# RP2040_MCU.net
KiCad netlist of a schematic drawn in Altium Designer
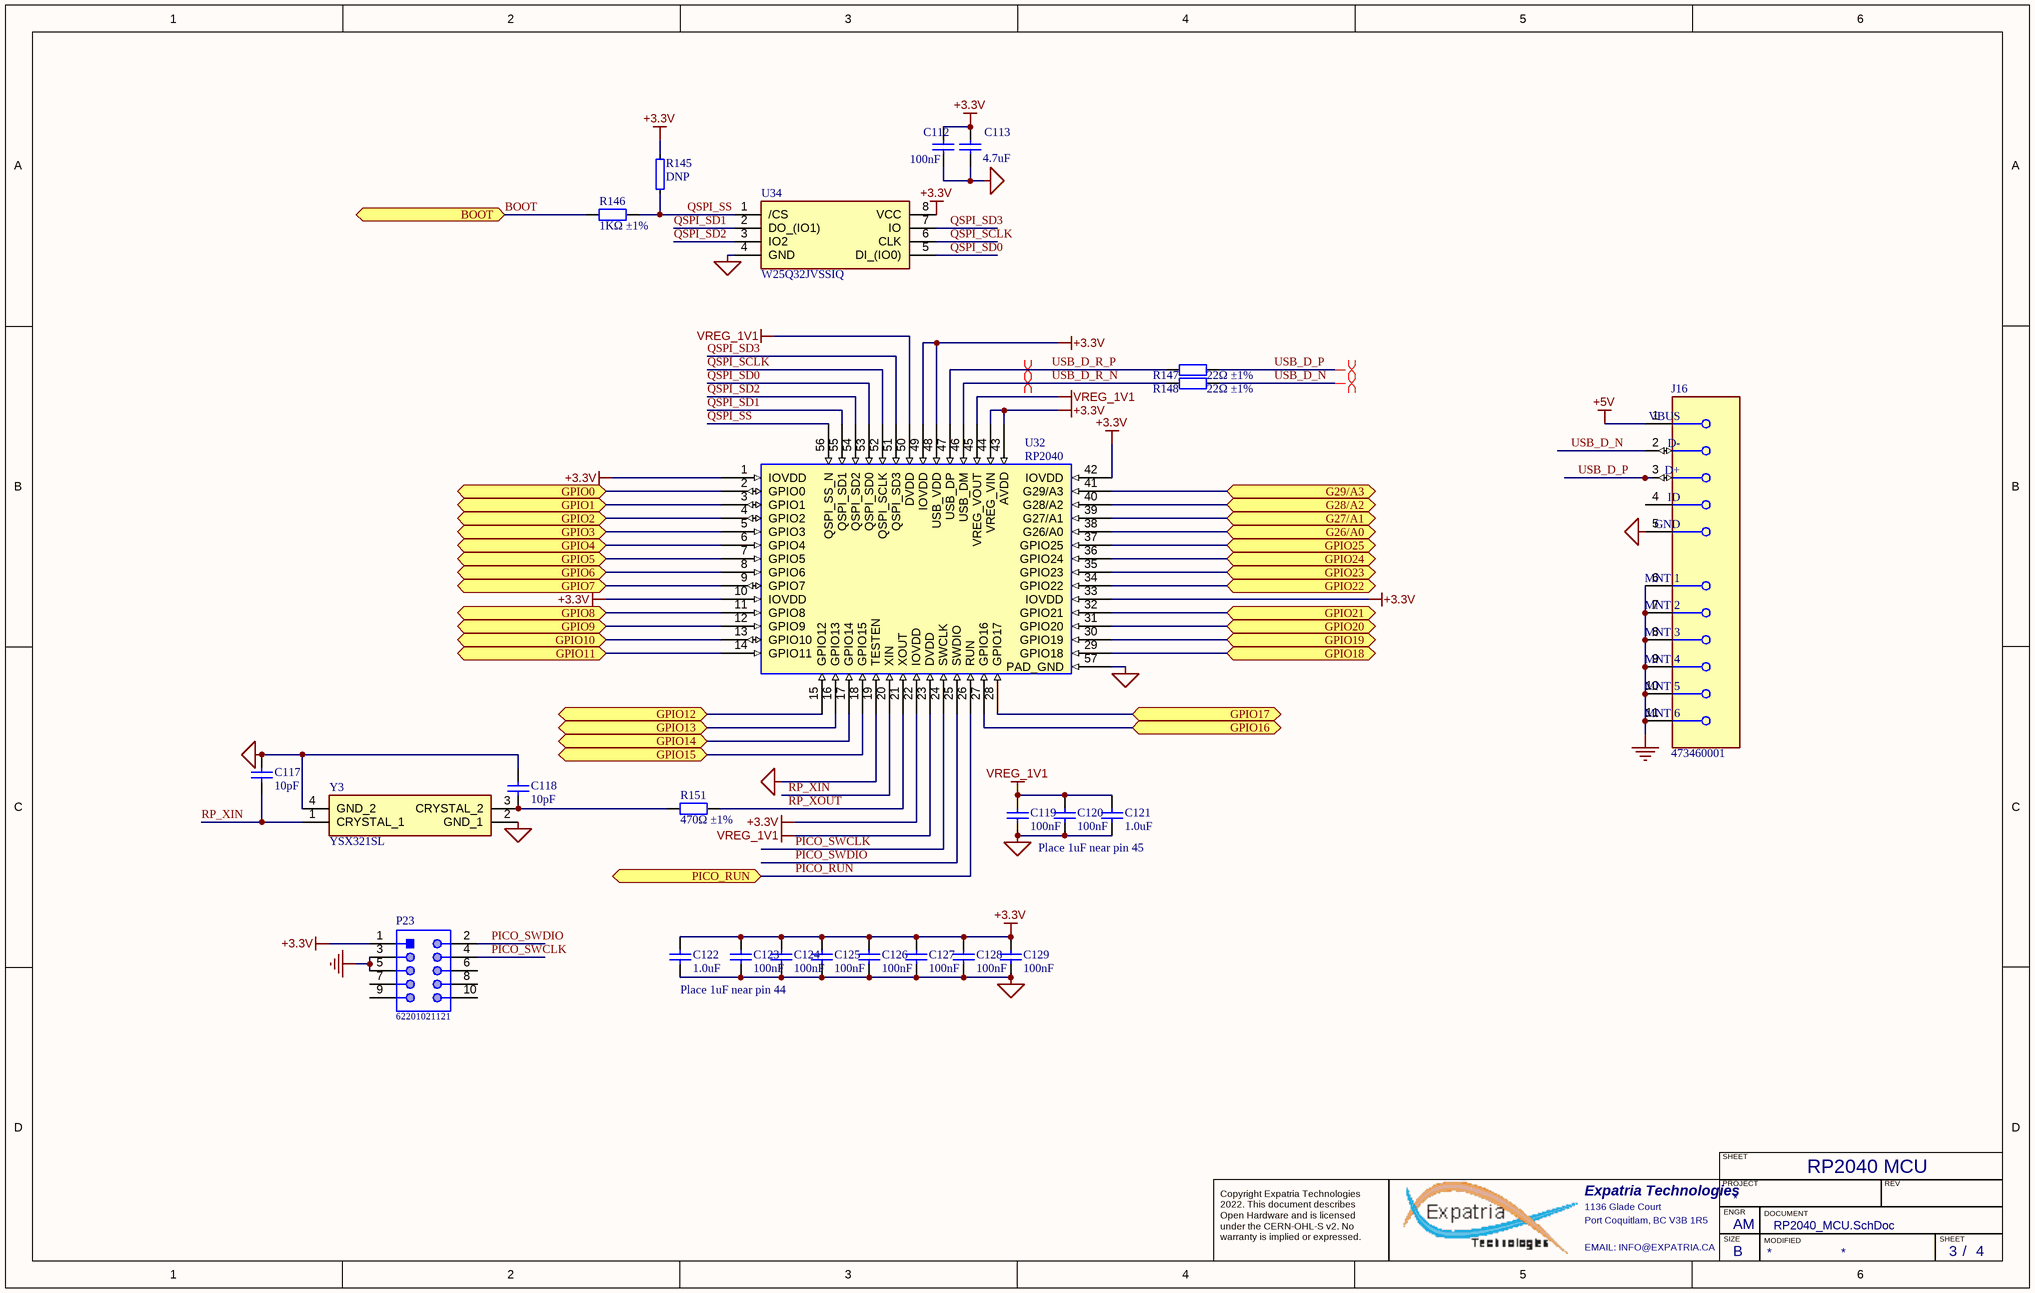
[diagram p0: RP2040_MCU.SchDoc]

(export (version "E")
  (design (tool "Eeschema 10.0.6"))
  (components
    (comp (ref "C112")
      (value "100nF")
      (footprint "0402_C")
      (description "Chip capacitors")
      (fields
        (field (name "MANUFACTURER") "Samsung Electro-Mechanics")
        (field (name "PARTNUMBER") "CL05B104KO5NNNC")
      )
      (libsource (lib "Cap") (part "0402 100nF (104) 10% 16V"))
    )
    (comp (ref "C113")
      (value "4.7uF")
      (footprint "0402_C")
      (description "Chip capacitor")
      (fields
        (field (name "MANUFACTURER") "Samsung Electro-Mechanics")
        (field (name "PARTNUMBER") "CL05A475MP5NRNC")
      )
      (libsource (lib "Cap") (part "0402 4.7uF (475) 20% 10V"))
    )
    (comp (ref "C117")
      (value "10pF")
      (footprint "0402_C")
      (description "Chip capacitors")
      (fields
        (field (name "MANUFACTURER") "Samsung Electro-Mechanics")
        (field (name "PARTNUMBER") "CL05C100JB5NNNC")
      )
      (libsource (lib "Cap") (part "0402 10pF (100) 5% 50V"))
    )
    (comp (ref "C118")
      (value "10pF")
      (footprint "0402_C")
      (description "Chip capacitors")
      (fields
        (field (name "MANUFACTURER") "Samsung Electro-Mechanics")
        (field (name "PARTNUMBER") "CL05C100JB5NNNC")
      )
      (libsource (lib "Cap") (part "0402 10pF (100) 5% 50V"))
    )
    (comp (ref "C119")
      (value "100nF")
      (footprint "0402_C")
      (description "Chip capacitors")
      (fields
        (field (name "MANUFACTURER") "Samsung Electro-Mechanics")
        (field (name "PARTNUMBER") "CL05B104KO5NNNC")
      )
      (libsource (lib "Cap") (part "0402 100nF (104) 10% 16V"))
    )
    (comp (ref "C120")
      (value "100nF")
      (footprint "0402_C")
      (description "Chip capacitors")
      (fields
        (field (name "MANUFACTURER") "Samsung Electro-Mechanics")
        (field (name "PARTNUMBER") "CL05B104KO5NNNC")
      )
      (libsource (lib "Cap") (part "0402 100nF (104) 10% 16V"))
    )
    (comp (ref "C121")
      (value "1.0uF")
      (footprint "0402_C")
      (description "Chip capacitor")
      (fields
        (field (name "MANUFACTURER") "Samsung Electro-Mechanics")
        (field (name "PARTNUMBER") "CL05A105KA5NQNC")
      )
      (libsource (lib "Cap") (part "0402 1.0uF (105) 10% 25V"))
    )
    (comp (ref "C122")
      (value "1.0uF")
      (footprint "0402_C")
      (description "Chip capacitor")
      (fields
        (field (name "MANUFACTURER") "Samsung Electro-Mechanics")
        (field (name "PARTNUMBER") "CL05A105KA5NQNC")
      )
      (libsource (lib "Cap") (part "0402 1.0uF (105) 10% 25V"))
    )
    (comp (ref "C123")
      (value "100nF")
      (footprint "0402_C")
      (description "Chip capacitors")
      (fields
        (field (name "MANUFACTURER") "Samsung Electro-Mechanics")
        (field (name "PARTNUMBER") "CL05B104KO5NNNC")
      )
      (libsource (lib "Cap") (part "0402 100nF (104) 10% 16V"))
    )
    (comp (ref "C124")
      (value "100nF")
      (footprint "0402_C")
      (description "Chip capacitors")
      (fields
        (field (name "MANUFACTURER") "Samsung Electro-Mechanics")
        (field (name "PARTNUMBER") "CL05B104KO5NNNC")
      )
      (libsource (lib "Cap") (part "0402 100nF (104) 10% 16V"))
    )
    (comp (ref "C125")
      (value "100nF")
      (footprint "0402_C")
      (description "Chip capacitors")
      (fields
        (field (name "MANUFACTURER") "Samsung Electro-Mechanics")
        (field (name "PARTNUMBER") "CL05B104KO5NNNC")
      )
      (libsource (lib "Cap") (part "0402 100nF (104) 10% 16V"))
    )
    (comp (ref "C126")
      (value "100nF")
      (footprint "0402_C")
      (description "Chip capacitors")
      (fields
        (field (name "MANUFACTURER") "Samsung Electro-Mechanics")
        (field (name "PARTNUMBER") "CL05B104KO5NNNC")
      )
      (libsource (lib "Cap") (part "0402 100nF (104) 10% 16V"))
    )
    (comp (ref "C127")
      (value "100nF")
      (footprint "0402_C")
      (description "Chip capacitors")
      (fields
        (field (name "MANUFACTURER") "Samsung Electro-Mechanics")
        (field (name "PARTNUMBER") "CL05B104KO5NNNC")
      )
      (libsource (lib "Cap") (part "0402 100nF (104) 10% 16V"))
    )
    (comp (ref "C128")
      (value "100nF")
      (footprint "0402_C")
      (description "Chip capacitors")
      (fields
        (field (name "MANUFACTURER") "Samsung Electro-Mechanics")
        (field (name "PARTNUMBER") "CL05B104KO5NNNC")
      )
      (libsource (lib "Cap") (part "0402 100nF (104) 10% 16V"))
    )
    (comp (ref "C129")
      (value "100nF")
      (footprint "0402_C")
      (description "Chip capacitors")
      (fields
        (field (name "MANUFACTURER") "Samsung Electro-Mechanics")
        (field (name "PARTNUMBER") "CL05B104KO5NNNC")
      )
      (libsource (lib "Cap") (part "0402 100nF (104) 10% 16V"))
    )
    (comp (ref "J16")
      (value "473460001")
      (footprint "FP-473460001-MFG")
      (description "CONN RCPT USB2.0 MICRO B SMD R/A")
      (fields
        (field (name "OCTOPART") "https://octopart.com/47346-0001-molex-7164928")
        (field (name "MANUFACTURER") "Molex")
      )
      (libsource (lib "Altium Content Vault") (part "53ae1f1d9b557310b43ca686e5bb76a"))
    )
    (comp (ref "P23")
      (value "62201021121")
      (footprint "62201021121")
      (description "THT Vertical Pin Header WR-PHD, Pitch 1.27 mm, Dual Row, 10 pins")
      (fields (field (name "MANUFACTURER") "Wurth Elektronik") (field (name "PUBLISHER") "WurthElektronik"))
      (libsource (lib "Altium Content Vault") (part "WE-CN-2P-M-R10"))
    )
    (comp (ref "R145")
      (value "DNP")
      (footprint "0402")
      (description "Resistor, ±5%, 0.05W")
      (fields (field (name "PART NUMBER") "R0201-0R") (field (name "PUBLISHER") "Nordic Semiconductor"))
      (libsource (lib "Passives") (part "RES"))
    )
    (comp (ref "R146")
      (value "1KΩ ±1%")
      (footprint "0402_R")
      (description "Chip resistor")
      (fields (field (name "MANUFACTURER") "Uniroyal Elec") (field (name "PARTNUMBER") "0402WGF1001TCE"))
      (libsource (lib "RES") (part "0402 1K (1001) 1%"))
    )
    (comp (ref "R147")
      (value "22Ω ±1%")
      (footprint "0402_R")
      (description "Chip resistor")
      (fields (field (name "MANUFACTURER") "Uniroyal Elec") (field (name "PARTNUMBER") "0402WGF220JTCE"))
      (libsource (lib "RES") (part "0402 22R (22R0) 1%"))
    )
    (comp (ref "R148")
      (value "22Ω ±1%")
      (footprint "0402_R")
      (description "Chip resistor")
      (fields (field (name "MANUFACTURER") "Uniroyal Elec") (field (name "PARTNUMBER") "0402WGF220JTCE"))
      (libsource (lib "RES") (part "0402 22R (22R0) 1%"))
    )
    (comp (ref "R151")
      (value "470Ω ±1%")
      (footprint "0402_R")
      (description "Chip resistor")
      (fields (field (name "MANUFACTURER") "Uniroyal Elec") (field (name "PARTNUMBER") "0402WGF4700TCE"))
      (libsource (lib "RES") (part "0402 470R (4700) 1%"))
    )
    (comp (ref "U32")
      (value "RP2040")
      (footprint "RP2040")
      (description "RP2040 First MCU from RPI")
      (libsource (lib "Universal_CNC_Breakout") (part "RP2040"))
    )
    (comp (ref "U34")
      (value "W25Q32JVSSIQ")
      (footprint "SamacSys:SOIC127P780X195-8N")
      (description "SPI Flash")
      (fields
        (field (name "MANUFACTURER_PART_NUMBER") "W25Q128JVSIQ TR")
        (field (name "MOUSER PART NUMBER") "454-W25Q128JVSIQTR")
      )
      (libsource (lib "*") (part "W25Q128JVSIQ_TR"))
    )
    (comp (ref "Y3")
      (value "YSX321SL")
      (footprint "SamacSys:YSX321SL")
      (description "Crystal or Oscillator")
      (libsource (lib "*") (part "YSX321SL"))
    )
  )
  (nets
    (net (code "1") (name "+3.3V") (class "Default")
      (node (ref "C112") (pin "2") (pinfunction "2_2") (pintype "passive"))
      (node (ref "C113") (pin "2") (pinfunction "2_2") (pintype "passive"))
      (node (ref "C122") (pin "2") (pinfunction "2_2") (pintype "passive"))
      (node (ref "C123") (pin "2") (pinfunction "2_2") (pintype "passive"))
      (node (ref "C124") (pin "2") (pinfunction "2_2") (pintype "passive"))
      (node (ref "C125") (pin "2") (pinfunction "2_2") (pintype "passive"))
      (node (ref "C126") (pin "2") (pinfunction "2_2") (pintype "passive"))
      (node (ref "C127") (pin "2") (pinfunction "2_2") (pintype "passive"))
      (node (ref "C128") (pin "2") (pinfunction "2_2") (pintype "passive"))
      (node (ref "C129") (pin "2") (pinfunction "2_2") (pintype "passive"))
      (node (ref "P23") (pin "1") (pinfunction "1_1") (pintype "passive"))
      (node (ref "R145") (pin "2") (pinfunction "2_2") (pintype "passive"))
      (node (ref "U32") (pin "1") (pinfunction "IOVDD_1") (pintype "input"))
      (node (ref "U32") (pin "10") (pinfunction "IOVDD_10") (pintype "input"))
      (node (ref "U32") (pin "22") (pinfunction "IOVDD_22") (pintype "input"))
      (node (ref "U32") (pin "33") (pinfunction "IOVDD_33") (pintype "input"))
      (node (ref "U32") (pin "42") (pinfunction "IOVDD_42") (pintype "input"))
      (node (ref "U32") (pin "43") (pinfunction "AVDD_43") (pintype "input"))
      (node (ref "U32") (pin "44") (pinfunction "VREG_VIN_44") (pintype "input"))
      (node (ref "U32") (pin "48") (pinfunction "USB_VDD_48") (pintype "input"))
      (node (ref "U32") (pin "49") (pinfunction "IOVDD_49") (pintype "input"))
      (node (ref "U34") (pin "8") (pinfunction "VCC_8") (pintype "passive"))
    )
    (net (code "2") (name "+5V") (class "Default")
      (node (ref "J16") (pin "1") (pinfunction "VBUS_1") (pintype "power_in"))
    )
    (net (code "3") (name "/BOOT") (class "Default")
      (node (ref "R146") (pin "1") (pinfunction "1_1") (pintype "passive"))
    )
    (net (code "4") (name "/G26{slash}A0") (class "Default")
      (node (ref "U32") (pin "38") (pinfunction "G26/A0_38") (pintype "input"))
    )
    (net (code "5") (name "/G27{slash}A1") (class "Default")
      (node (ref "U32") (pin "39") (pinfunction "G27/A1_39") (pintype "input"))
    )
    (net (code "6") (name "/G28{slash}A2") (class "Default")
      (node (ref "U32") (pin "40") (pinfunction "G28/A2_40") (pintype "input"))
    )
    (net (code "7") (name "/G29{slash}A3") (class "Default")
      (node (ref "U32") (pin "41") (pinfunction "G29/A3_41") (pintype "input"))
    )
    (net (code "8") (name "/GPIO0") (class "Default")
      (node (ref "U32") (pin "2") (pinfunction "GPIO0_2") (pintype "bidirectional"))
    )
    (net (code "9") (name "/GPIO1") (class "Default")
      (node (ref "U32") (pin "3") (pinfunction "GPIO1_3") (pintype "bidirectional"))
    )
    (net (code "10") (name "/GPIO2") (class "Default")
      (node (ref "U32") (pin "4") (pinfunction "GPIO2_4") (pintype "bidirectional"))
    )
    (net (code "11") (name "/GPIO3") (class "Default")
      (node (ref "U32") (pin "5") (pinfunction "GPIO3_5") (pintype "input"))
    )
    (net (code "12") (name "/GPIO4") (class "Default")
      (node (ref "U32") (pin "6") (pinfunction "GPIO4_6") (pintype "input"))
    )
    (net (code "13") (name "/GPIO5") (class "Default")
      (node (ref "U32") (pin "7") (pinfunction "GPIO5_7") (pintype "input"))
    )
    (net (code "14") (name "/GPIO6") (class "Default")
      (node (ref "U32") (pin "8") (pinfunction "GPIO6_8") (pintype "input"))
    )
    (net (code "15") (name "/GPIO7") (class "Default")
      (node (ref "U32") (pin "9") (pinfunction "GPIO7_9") (pintype "bidirectional"))
    )
    (net (code "16") (name "/GPIO8") (class "Default")
      (node (ref "U32") (pin "11") (pinfunction "GPIO8_11") (pintype "input"))
    )
    (net (code "17") (name "/GPIO9") (class "Default")
      (node (ref "U32") (pin "12") (pinfunction "GPIO9_12") (pintype "input"))
    )
    (net (code "18") (name "/GPIO10") (class "Default")
      (node (ref "U32") (pin "13") (pinfunction "GPIO10_13") (pintype "bidirectional"))
    )
    (net (code "19") (name "/GPIO11") (class "Default")
      (node (ref "U32") (pin "14") (pinfunction "GPIO11_14") (pintype "input"))
    )
    (net (code "20") (name "/GPIO12") (class "Default")
      (node (ref "U32") (pin "15") (pinfunction "GPIO12_15") (pintype "input"))
    )
    (net (code "21") (name "/GPIO13") (class "Default")
      (node (ref "U32") (pin "16") (pinfunction "GPIO13_16") (pintype "input"))
    )
    (net (code "22") (name "/GPIO14") (class "Default")
      (node (ref "U32") (pin "17") (pinfunction "GPIO14_17") (pintype "input"))
    )
    (net (code "23") (name "/GPIO15") (class "Default")
      (node (ref "U32") (pin "18") (pinfunction "GPIO15_18") (pintype "input"))
    )
    (net (code "24") (name "/GPIO16") (class "Default")
      (node (ref "U32") (pin "27") (pinfunction "GPIO16_27") (pintype "input"))
    )
    (net (code "25") (name "/GPIO17") (class "Default")
      (node (ref "U32") (pin "28") (pinfunction "GPIO17_28") (pintype "input"))
    )
    (net (code "26") (name "/GPIO18") (class "Default")
      (node (ref "U32") (pin "29") (pinfunction "GPIO18_29") (pintype "input"))
    )
    (net (code "27") (name "/GPIO19") (class "Default")
      (node (ref "U32") (pin "30") (pinfunction "GPIO19_30") (pintype "input"))
    )
    (net (code "28") (name "/GPIO20") (class "Default")
      (node (ref "U32") (pin "31") (pinfunction "GPIO20_31") (pintype "input"))
    )
    (net (code "29") (name "/GPIO21") (class "Default")
      (node (ref "U32") (pin "32") (pinfunction "GPIO21_32") (pintype "input"))
    )
    (net (code "30") (name "/GPIO22") (class "Default")
      (node (ref "U32") (pin "34") (pinfunction "GPIO22_34") (pintype "input"))
    )
    (net (code "31") (name "/GPIO23") (class "Default")
      (node (ref "U32") (pin "35") (pinfunction "GPIO23_35") (pintype "input"))
    )
    (net (code "32") (name "/GPIO24") (class "Default")
      (node (ref "U32") (pin "36") (pinfunction "GPIO24_36") (pintype "input"))
    )
    (net (code "33") (name "/GPIO25") (class "Default")
      (node (ref "U32") (pin "37") (pinfunction "GPIO25_37") (pintype "input"))
    )
    (net (code "34") (name "/PICO_RUN") (class "Default")
      (node (ref "U32") (pin "26") (pinfunction "RUN_26") (pintype "input"))
    )
    (net (code "35") (name "/PICO_SWCLK") (class "Default")
      (node (ref "P23") (pin "4") (pinfunction "4_4") (pintype "passive"))
      (node (ref "U32") (pin "24") (pinfunction "SWCLK_24") (pintype "input"))
    )
    (net (code "36") (name "/PICO_SWDIO") (class "Default")
      (node (ref "P23") (pin "2") (pinfunction "2_2") (pintype "passive"))
      (node (ref "U32") (pin "25") (pinfunction "SWDIO_25") (pintype "input"))
    )
    (net (code "37") (name "/QSPI_SCLK") (class "Default")
      (node (ref "U32") (pin "52") (pinfunction "QSPI_SCLK_52") (pintype "input"))
      (node (ref "U34") (pin "6") (pinfunction "CLK_6") (pintype "passive"))
    )
    (net (code "38") (name "/QSPI_SD0") (class "Default")
      (node (ref "U32") (pin "53") (pinfunction "QSPI_SD0_53") (pintype "input"))
      (node (ref "U34") (pin "5") (pinfunction "DI_(IO0)_5") (pintype "passive"))
    )
    (net (code "39") (name "/QSPI_SD1") (class "Default")
      (node (ref "U32") (pin "55") (pinfunction "QSPI_SD1_55") (pintype "input"))
      (node (ref "U34") (pin "2") (pinfunction "DO_(IO1)_2") (pintype "passive"))
    )
    (net (code "40") (name "/QSPI_SD2") (class "Default")
      (node (ref "U32") (pin "54") (pinfunction "QSPI_SD2_54") (pintype "input"))
      (node (ref "U34") (pin "3") (pinfunction "IO2_3") (pintype "passive"))
    )
    (net (code "41") (name "/QSPI_SD3") (class "Default")
      (node (ref "U32") (pin "51") (pinfunction "QSPI_SD3_51") (pintype "input"))
      (node (ref "U34") (pin "7") (pinfunction "IO_7") (pintype "passive"))
    )
    (net (code "42") (name "/QSPI_SS") (class "Default")
      (node (ref "R145") (pin "1") (pinfunction "1_1") (pintype "passive"))
      (node (ref "R146") (pin "2") (pinfunction "2_2") (pintype "passive"))
      (node (ref "U32") (pin "56") (pinfunction "QSPI_SS_N_56") (pintype "input"))
      (node (ref "U34") (pin "1") (pinfunction "/CS_1") (pintype "passive"))
    )
    (net (code "43") (name "/RP_XIN") (class "Default")
      (node (ref "C117") (pin "1") (pinfunction "1_1") (pintype "passive"))
      (node (ref "U32") (pin "20") (pinfunction "XIN_20") (pintype "input"))
      (node (ref "Y3") (pin "1") (pinfunction "CRYSTAL_1_1") (pintype "passive"))
    )
    (net (code "44") (name "/RP_XOUT") (class "Default")
      (node (ref "R151") (pin "2") (pinfunction "2_2") (pintype "passive"))
      (node (ref "U32") (pin "21") (pinfunction "XOUT_21") (pintype "input"))
    )
    (net (code "45") (name "/USB_D_N") (class "Default")
      (node (ref "J16") (pin "2") (pinfunction "D-_2") (pintype "bidirectional"))
      (node (ref "R148") (pin "1") (pinfunction "1_1") (pintype "passive"))
    )
    (net (code "46") (name "/USB_D_P") (class "Default")
      (node (ref "J16") (pin "3") (pinfunction "D+_3") (pintype "bidirectional"))
      (node (ref "R147") (pin "1") (pinfunction "1_1") (pintype "passive"))
    )
    (net (code "47") (name "/USB_D_R_N") (class "Default")
      (node (ref "R148") (pin "2") (pinfunction "2_2") (pintype "passive"))
      (node (ref "U32") (pin "46") (pinfunction "USB_DM_46") (pintype "input"))
    )
    (net (code "48") (name "/USB_D_R_P") (class "Default")
      (node (ref "R147") (pin "2") (pinfunction "2_2") (pintype "passive"))
      (node (ref "U32") (pin "47") (pinfunction "USB_DP_47") (pintype "input"))
    )
    (net (code "49") (name "GND") (class "Default")
      (node (ref "J16") (pin "10") (pinfunction "MNT_5_10") (pintype "passive"))
      (node (ref "J16") (pin "11") (pinfunction "MNT_6_11") (pintype "passive"))
      (node (ref "J16") (pin "6") (pinfunction "MNT_1_6") (pintype "passive"))
      (node (ref "J16") (pin "7") (pinfunction "MNT_2_7") (pintype "passive"))
      (node (ref "J16") (pin "8") (pinfunction "MNT_3_8") (pintype "passive"))
      (node (ref "J16") (pin "9") (pinfunction "MNT_4_9") (pintype "passive"))
      (node (ref "P23") (pin "3") (pinfunction "3_3") (pintype "passive"))
      (node (ref "P23") (pin "5") (pinfunction "5_5") (pintype "passive"))
    )
    (net (code "50") (name "MCU_GND") (class "Default")
      (node (ref "C112") (pin "1") (pinfunction "1_1") (pintype "passive"))
      (node (ref "C113") (pin "1") (pinfunction "1_1") (pintype "passive"))
      (node (ref "C117") (pin "2") (pinfunction "2_2") (pintype "passive"))
      (node (ref "C118") (pin "2") (pinfunction "2_2") (pintype "passive"))
      (node (ref "C119") (pin "1") (pinfunction "1_1") (pintype "passive"))
      (node (ref "C120") (pin "1") (pinfunction "1_1") (pintype "passive"))
      (node (ref "C121") (pin "1") (pinfunction "1_1") (pintype "passive"))
      (node (ref "C122") (pin "1") (pinfunction "1_1") (pintype "passive"))
      (node (ref "C123") (pin "1") (pinfunction "1_1") (pintype "passive"))
      (node (ref "C124") (pin "1") (pinfunction "1_1") (pintype "passive"))
      (node (ref "C125") (pin "1") (pinfunction "1_1") (pintype "passive"))
      (node (ref "C126") (pin "1") (pinfunction "1_1") (pintype "passive"))
      (node (ref "C127") (pin "1") (pinfunction "1_1") (pintype "passive"))
      (node (ref "C128") (pin "1") (pinfunction "1_1") (pintype "passive"))
      (node (ref "C129") (pin "1") (pinfunction "1_1") (pintype "passive"))
      (node (ref "J16") (pin "5") (pinfunction "GND_5") (pintype "power_in"))
      (node (ref "U32") (pin "19") (pinfunction "TESTEN_19") (pintype "input"))
      (node (ref "U32") (pin "57") (pinfunction "PAD_GND_57") (pintype "input"))
      (node (ref "U34") (pin "4") (pinfunction "GND_4") (pintype "passive"))
      (node (ref "Y3") (pin "2") (pinfunction "GND_1_2") (pintype "passive"))
      (node (ref "Y3") (pin "4") (pinfunction "GND_2_4") (pintype "passive"))
    )
    (net (code "51") (name "Net-(Y3-CRYSTAL_2)") (class "Default")
      (node (ref "C118") (pin "1") (pinfunction "1_1") (pintype "passive"))
      (node (ref "R151") (pin "1") (pinfunction "1_1") (pintype "passive"))
      (node (ref "Y3") (pin "3") (pinfunction "CRYSTAL_2_3") (pintype "passive"))
    )
    (net (code "52") (name "VREG_1V1") (class "Default")
      (node (ref "C119") (pin "2") (pinfunction "2_2") (pintype "passive"))
      (node (ref "C120") (pin "2") (pinfunction "2_2") (pintype "passive"))
      (node (ref "C121") (pin "2") (pinfunction "2_2") (pintype "passive"))
      (node (ref "U32") (pin "23") (pinfunction "DVDD_23") (pintype "input"))
      (node (ref "U32") (pin "45") (pinfunction "VREG_VOUT_45") (pintype "input"))
      (node (ref "U32") (pin "50") (pinfunction "DVDD_50") (pintype "input"))
    )
    (net (code "53") (name "unconnected-(J16-ID-Pad4)") (class "Default")
      (node (ref "J16") (pin "4") (pinfunction "ID_4") (pintype "passive"))
    )
    (net (code "54") (name "unconnected-(P23-Pad6)") (class "Default")
      (node (ref "P23") (pin "6") (pinfunction "6_6") (pintype "passive"))
    )
    (net (code "55") (name "unconnected-(P23-Pad7)") (class "Default")
      (node (ref "P23") (pin "7") (pinfunction "7_7") (pintype "passive"))
    )
    (net (code "56") (name "unconnected-(P23-Pad8)") (class "Default")
      (node (ref "P23") (pin "8") (pinfunction "8_8") (pintype "passive"))
    )
    (net (code "57") (name "unconnected-(P23-Pad9)") (class "Default")
      (node (ref "P23") (pin "9") (pinfunction "9_9") (pintype "passive"))
    )
    (net (code "58") (name "unconnected-(P23-Pad10)") (class "Default")
      (node (ref "P23") (pin "10") (pinfunction "10_10") (pintype "passive"))
    )
  )
)
